# SYN6288Pcb.net
KiCad netlist of a schematic drawn in Altium Designer
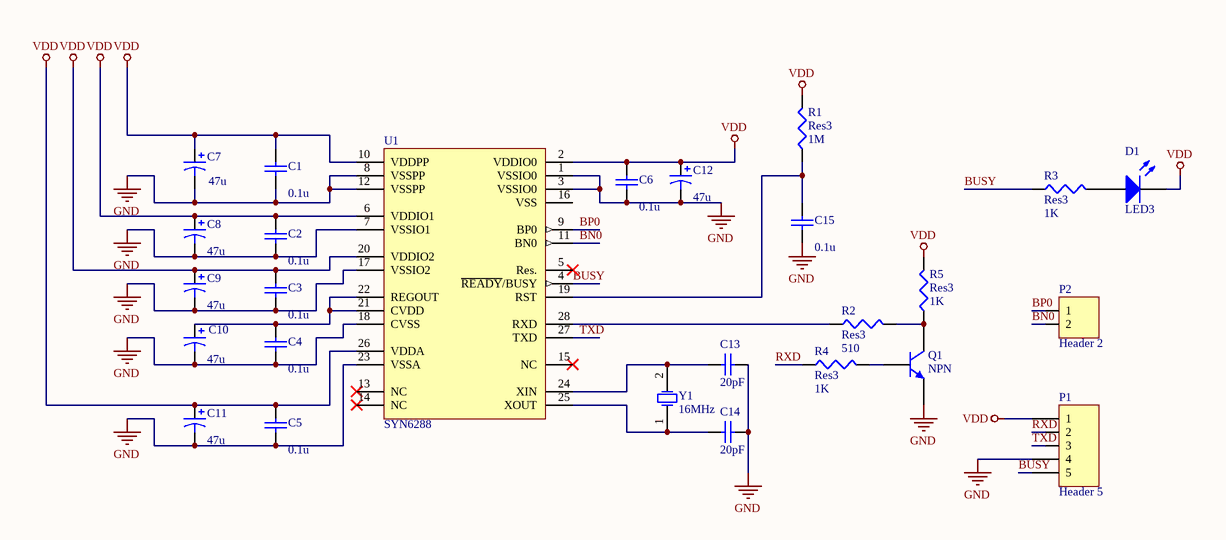
[diagram p0: SYN6288Pcb.SchDoc]

(export (version "E")
  (design (tool "Eeschema 10.0.6"))
  (components
    (comp (ref "C1")
      (value "0.1u")
      (footprint "C1206")
      (description "Capacitor (Semiconductor SIM Model)")
      (fields (field (name "Comment") "Cap Semi") (field (name "PUBLISHER") "Altium Limited"))
      (libsource (lib "Miscellaneous Devices") (part "Cap Semi"))
    )
    (comp (ref "C2")
      (value "0.1u")
      (footprint "C1206")
      (description "Capacitor (Semiconductor SIM Model)")
      (fields (field (name "Comment") "Cap Semi") (field (name "PUBLISHER") "Altium Limited"))
      (libsource (lib "Miscellaneous Devices") (part "Cap Semi"))
    )
    (comp (ref "C3")
      (value "0.1u")
      (footprint "C1206")
      (description "Capacitor (Semiconductor SIM Model)")
      (fields (field (name "Comment") "Cap Semi") (field (name "PUBLISHER") "Altium Limited"))
      (libsource (lib "Miscellaneous Devices") (part "Cap Semi"))
    )
    (comp (ref "C4")
      (value "0.1u")
      (footprint "C1206")
      (description "Capacitor (Semiconductor SIM Model)")
      (fields (field (name "Comment") "Cap Semi") (field (name "PUBLISHER") "Altium Limited"))
      (libsource (lib "Miscellaneous Devices") (part "Cap Semi"))
    )
    (comp (ref "C5")
      (value "0.1u")
      (footprint "C1206")
      (description "Capacitor (Semiconductor SIM Model)")
      (fields (field (name "Comment") "Cap Semi") (field (name "PUBLISHER") "Altium Limited"))
      (libsource (lib "Miscellaneous Devices") (part "Cap Semi"))
    )
    (comp (ref "C6")
      (value "0.1u")
      (footprint "C1206")
      (description "Capacitor (Semiconductor SIM Model)")
      (fields (field (name "Comment") "Cap Semi") (field (name "PUBLISHER") "Altium Limited"))
      (libsource (lib "Miscellaneous Devices") (part "Cap Semi"))
    )
    (comp (ref "C7")
      (value "47u")
      (footprint "C0805")
      (description "Polarized Capacitor (Surface Mount)")
      (fields (field (name "Comment") "Cap Pol3") (field (name "PUBLISHER") "Altium Limited"))
      (libsource (lib "Miscellaneous Devices") (part "Cap Pol3"))
    )
    (comp (ref "C8")
      (value "47u")
      (footprint "C0805")
      (description "Polarized Capacitor (Surface Mount)")
      (fields (field (name "Comment") "Cap Pol3") (field (name "PUBLISHER") "Altium Limited"))
      (libsource (lib "Miscellaneous Devices") (part "Cap Pol3"))
    )
    (comp (ref "C9")
      (value "47u")
      (footprint "C0805")
      (description "Polarized Capacitor (Surface Mount)")
      (fields (field (name "Comment") "Cap Pol3") (field (name "PUBLISHER") "Altium Limited"))
      (libsource (lib "Miscellaneous Devices") (part "Cap Pol3"))
    )
    (comp (ref "C10")
      (value "47u")
      (footprint "C0805")
      (description "Polarized Capacitor (Surface Mount)")
      (fields (field (name "Comment") "Cap Pol3") (field (name "PUBLISHER") "Altium Limited"))
      (libsource (lib "Miscellaneous Devices") (part "Cap Pol3"))
    )
    (comp (ref "C11")
      (value "47u")
      (footprint "C0805")
      (description "Polarized Capacitor (Surface Mount)")
      (fields (field (name "Comment") "Cap Pol3") (field (name "PUBLISHER") "Altium Limited"))
      (libsource (lib "Miscellaneous Devices") (part "Cap Pol3"))
    )
    (comp (ref "C12")
      (value "47u")
      (footprint "C0805")
      (description "Polarized Capacitor (Surface Mount)")
      (fields (field (name "Comment") "Cap Pol3") (field (name "PUBLISHER") "Altium Limited"))
      (libsource (lib "Miscellaneous Devices") (part "Cap Pol3"))
    )
    (comp (ref "C13")
      (value "20pF")
      (footprint "C1206")
      (description "Capacitor (Semiconductor SIM Model)")
      (fields (field (name "Comment") "Cap Semi") (field (name "PUBLISHER") "Altium Limited"))
      (libsource (lib "Miscellaneous Devices") (part "Cap Semi"))
    )
    (comp (ref "C14")
      (value "20pF")
      (footprint "C1206")
      (description "Capacitor (Semiconductor SIM Model)")
      (fields (field (name "Comment") "Cap Semi") (field (name "PUBLISHER") "Altium Limited"))
      (libsource (lib "Miscellaneous Devices") (part "Cap Semi"))
    )
    (comp (ref "C15")
      (value "0.1u")
      (footprint "C1206")
      (description "Capacitor (Semiconductor SIM Model)")
      (fields (field (name "Comment") "Cap Semi") (field (name "PUBLISHER") "Altium Limited"))
      (libsource (lib "Miscellaneous Devices") (part "Cap Semi"))
    )
    (comp (ref "D1")
      (value "LED3")
      (footprint "3.5X2.8X1.9")
      (description "Typical BLUE SiC LED")
      (fields (field (name "PUBLISHER") "Altium Limited"))
      (libsource (lib "Miscellaneous Devices") (part "LED3"))
    )
    (comp (ref "P1")
      (value "Header 5")
      (footprint "HDR1X5")
      (description "Header, 5-Pin")
      (fields (field (name "PUBLISHER") "Altium Limited"))
      (libsource (lib "Miscellaneous Connectors") (part "Header 5"))
    )
    (comp (ref "P2")
      (value "Header 2")
      (footprint "HDR1X2")
      (description "Header, 2-Pin")
      (fields (field (name "PUBLISHER") "Altium Limited"))
      (libsource (lib "Miscellaneous Connectors") (part "Header 2"))
    )
    (comp (ref "Q1")
      (value "NPN")
      (footprint "TO-226-AA")
      (description "NPN Bipolar Transistor")
      (fields (field (name "PUBLISHER") "Altium Limited"))
      (libsource (lib "Miscellaneous Devices") (part "NPN"))
    )
    (comp (ref "R1")
      (value "Res3")
      (footprint "J1-0603")
      (description "Resistor")
      (fields (field (name "ALTIUM_VALUE") "1M") (field (name "PUBLISHER") "Altium Limited"))
      (libsource (lib "Miscellaneous Devices") (part "Res3"))
    )
    (comp (ref "R2")
      (value "Res3")
      (footprint "J1-0603")
      (description "Resistor")
      (fields (field (name "ALTIUM_VALUE") "510") (field (name "PUBLISHER") "Altium Limited"))
      (libsource (lib "Miscellaneous Devices") (part "Res3"))
    )
    (comp (ref "R3")
      (value "Res3")
      (footprint "J1-0603")
      (description "Resistor")
      (fields (field (name "ALTIUM_VALUE") "1K") (field (name "PUBLISHER") "Altium Limited"))
      (libsource (lib "Miscellaneous Devices") (part "Res3"))
    )
    (comp (ref "R4")
      (value "Res3")
      (footprint "J1-0603")
      (description "Resistor")
      (fields (field (name "ALTIUM_VALUE") "1K") (field (name "PUBLISHER") "Altium Limited"))
      (libsource (lib "Miscellaneous Devices") (part "Res3"))
    )
    (comp (ref "R5")
      (value "Res3")
      (footprint "J1-0603")
      (description "Resistor")
      (fields (field (name "ALTIUM_VALUE") "1K") (field (name "PUBLISHER") "Altium Limited"))
      (libsource (lib "Miscellaneous Devices") (part "Res3"))
    )
    (comp (ref "U1") (value "SYN6288") (footprint "SYN6288") (libsource (lib "SYN6288") (part "SYN6288")))
    (comp (ref "Y1")
      (value "16MHz")
      (footprint "R38")
      (description "Crystal Oscillator")
      (fields (field (name "PUBLISHER") "Altium Limited"))
      (libsource (lib "Miscellaneous Devices") (part "XTAL"))
    )
  )
  (nets
    (net (code "1") (name "/BN0") (class "Default")
      (node (ref "P2") (pin "2") (pinfunction "2_2") (pintype "passive"))
      (node (ref "U1") (pin "11") (pinfunction "BN0_11") (pintype "output"))
    )
    (net (code "2") (name "/BP0") (class "Default")
      (node (ref "P2") (pin "1") (pinfunction "1_1") (pintype "passive"))
      (node (ref "U1") (pin "9") (pinfunction "BP0_9") (pintype "output"))
    )
    (net (code "3") (name "/BUSY") (class "Default")
      (node (ref "P1") (pin "5") (pinfunction "5_5") (pintype "passive"))
      (node (ref "R3") (pin "1") (pinfunction "1_1") (pintype "passive"))
      (node (ref "U1") (pin "4") (pinfunction "~{READY}/BUSY_4") (pintype "output"))
    )
    (net (code "4") (name "/RXD") (class "Default")
      (node (ref "P1") (pin "2") (pinfunction "2_2") (pintype "passive"))
      (node (ref "R4") (pin "1") (pinfunction "1_1") (pintype "passive"))
    )
    (net (code "5") (name "/TXD") (class "Default")
      (node (ref "P1") (pin "3") (pinfunction "3_3") (pintype "passive"))
      (node (ref "U1") (pin "27") (pinfunction "TXD_27") (pintype "passive"))
    )
    (net (code "6") (name "GND") (class "Default")
      (node (ref "C1") (pin "1") (pinfunction "1_1") (pintype "passive"))
      (node (ref "C10") (pin "2") (pinfunction "2_2") (pintype "passive"))
      (node (ref "C11") (pin "2") (pinfunction "2_2") (pintype "passive"))
      (node (ref "C12") (pin "2") (pinfunction "2_2") (pintype "passive"))
      (node (ref "C13") (pin "2") (pinfunction "2_2") (pintype "passive"))
      (node (ref "C14") (pin "2") (pinfunction "2_2") (pintype "passive"))
      (node (ref "C15") (pin "1") (pinfunction "1_1") (pintype "passive"))
      (node (ref "C2") (pin "1") (pinfunction "1_1") (pintype "passive"))
      (node (ref "C3") (pin "1") (pinfunction "1_1") (pintype "passive"))
      (node (ref "C4") (pin "1") (pinfunction "1_1") (pintype "passive"))
      (node (ref "C5") (pin "1") (pinfunction "1_1") (pintype "passive"))
      (node (ref "C6") (pin "1") (pinfunction "1_1") (pintype "passive"))
      (node (ref "C7") (pin "2") (pinfunction "2_2") (pintype "passive"))
      (node (ref "C8") (pin "2") (pinfunction "2_2") (pintype "passive"))
      (node (ref "C9") (pin "2") (pinfunction "2_2") (pintype "passive"))
      (node (ref "P1") (pin "4") (pinfunction "4_4") (pintype "passive"))
      (node (ref "Q1") (pin "3") (pinfunction "E_3") (pintype "passive"))
      (node (ref "U1") (pin "1") (pinfunction "VSSIO0_1") (pintype "power_in"))
      (node (ref "U1") (pin "12") (pinfunction "VSSPP_12") (pintype "power_in"))
      (node (ref "U1") (pin "17") (pinfunction "VSSIO2_17") (pintype "power_in"))
      (node (ref "U1") (pin "18") (pinfunction "CVSS_18") (pintype "power_in"))
      (node (ref "U1") (pin "23") (pinfunction "VSSA_23") (pintype "power_in"))
      (node (ref "U1") (pin "3") (pinfunction "VSSIO0_3") (pintype "power_in"))
      (node (ref "U1") (pin "7") (pinfunction "VSSIO1_7") (pintype "power_in"))
      (node (ref "U1") (pin "8") (pinfunction "VSSPP_8") (pintype "power_in"))
    )
    (net (code "7") (name "Net-(D1-A)") (class "Default")
      (node (ref "D1") (pin "1") (pinfunction "A_1") (pintype "passive"))
      (node (ref "R3") (pin "2") (pinfunction "2_2") (pintype "passive"))
    )
    (net (code "8") (name "Net-(Q1-B)") (class "Default")
      (node (ref "Q1") (pin "2") (pinfunction "B_2") (pintype "passive"))
      (node (ref "R4") (pin "2") (pinfunction "2_2") (pintype "passive"))
    )
    (net (code "9") (name "Net-(Q1-C)") (class "Default")
      (node (ref "Q1") (pin "1") (pinfunction "C_1") (pintype "passive"))
      (node (ref "R2") (pin "2") (pinfunction "2_2") (pintype "passive"))
      (node (ref "R5") (pin "1") (pinfunction "1_1") (pintype "passive"))
    )
    (net (code "10") (name "Net-(U1-CVDD)") (class "Default")
      (node (ref "C10") (pin "1") (pinfunction "1_1") (pintype "passive"))
      (node (ref "C4") (pin "2") (pinfunction "2_2") (pintype "passive"))
      (node (ref "U1") (pin "21") (pinfunction "CVDD_21") (pintype "power_in"))
      (node (ref "U1") (pin "22") (pinfunction "REGOUT_22") (pintype "power_in"))
    )
    (net (code "11") (name "Net-(U1-RST)") (class "Default")
      (node (ref "C15") (pin "2") (pinfunction "2_2") (pintype "passive"))
      (node (ref "R1") (pin "1") (pinfunction "1_1") (pintype "passive"))
      (node (ref "U1") (pin "19") (pinfunction "RST_19") (pintype "passive"))
    )
    (net (code "12") (name "Net-(U1-RXD)") (class "Default")
      (node (ref "R2") (pin "1") (pinfunction "1_1") (pintype "passive"))
      (node (ref "U1") (pin "28") (pinfunction "RXD_28") (pintype "passive"))
    )
    (net (code "13") (name "Net-(U1-XIN)") (class "Default")
      (node (ref "C13") (pin "1") (pinfunction "1_1") (pintype "passive"))
      (node (ref "U1") (pin "24") (pinfunction "XIN_24") (pintype "passive"))
      (node (ref "Y1") (pin "2") (pinfunction "OSC2_2") (pintype "passive"))
    )
    (net (code "14") (name "Net-(U1-XOUT)") (class "Default")
      (node (ref "C14") (pin "1") (pinfunction "1_1") (pintype "passive"))
      (node (ref "U1") (pin "25") (pinfunction "XOUT_25") (pintype "passive"))
      (node (ref "Y1") (pin "1") (pinfunction "OSC1_1") (pintype "passive"))
    )
    (net (code "15") (name "VDD") (class "Default")
      (node (ref "C1") (pin "2") (pinfunction "2_2") (pintype "passive"))
      (node (ref "C11") (pin "1") (pinfunction "1_1") (pintype "passive"))
      (node (ref "C12") (pin "1") (pinfunction "1_1") (pintype "passive"))
      (node (ref "C2") (pin "2") (pinfunction "2_2") (pintype "passive"))
      (node (ref "C3") (pin "2") (pinfunction "2_2") (pintype "passive"))
      (node (ref "C5") (pin "2") (pinfunction "2_2") (pintype "passive"))
      (node (ref "C6") (pin "2") (pinfunction "2_2") (pintype "passive"))
      (node (ref "C7") (pin "1") (pinfunction "1_1") (pintype "passive"))
      (node (ref "C8") (pin "1") (pinfunction "1_1") (pintype "passive"))
      (node (ref "C9") (pin "1") (pinfunction "1_1") (pintype "passive"))
      (node (ref "D1") (pin "2") (pinfunction "K_2") (pintype "passive"))
      (node (ref "P1") (pin "1") (pinfunction "1_1") (pintype "passive"))
      (node (ref "R1") (pin "2") (pinfunction "2_2") (pintype "passive"))
      (node (ref "R5") (pin "2") (pinfunction "2_2") (pintype "passive"))
      (node (ref "U1") (pin "10") (pinfunction "VDDPP_10") (pintype "power_in"))
      (node (ref "U1") (pin "2") (pinfunction "VDDIO0_2") (pintype "power_in"))
      (node (ref "U1") (pin "20") (pinfunction "VDDIO2_20") (pintype "power_in"))
      (node (ref "U1") (pin "26") (pinfunction "VDDA_26") (pintype "power_in"))
      (node (ref "U1") (pin "6") (pinfunction "VDDIO1_6") (pintype "power_in"))
    )
    (net (code "16") (name "unconnected-(U1-NC-Pad13)") (class "Default")
      (node (ref "U1") (pin "13") (pinfunction "NC_13") (pintype "passive+no_connect"))
    )
    (net (code "17") (name "unconnected-(U1-NC-Pad14)") (class "Default")
      (node (ref "U1") (pin "14") (pinfunction "NC_14") (pintype "passive+no_connect"))
    )
    (net (code "18") (name "unconnected-(U1-NC-Pad15)") (class "Default")
      (node (ref "U1") (pin "15") (pinfunction "NC_15") (pintype "passive+no_connect"))
    )
    (net (code "19") (name "unconnected-(U1-Res.-Pad5)") (class "Default")
      (node (ref "U1") (pin "5") (pinfunction "Res._5") (pintype "passive+no_connect"))
    )
    (net (code "20") (name "unconnected-(U1-VSS-Pad16)") (class "Default")
      (node (ref "U1") (pin "16") (pinfunction "VSS_16") (pintype "power_in"))
    )
  )
)
